# QuadroOLED.net
KiCad netlist of a schematic drawn in EAGLE
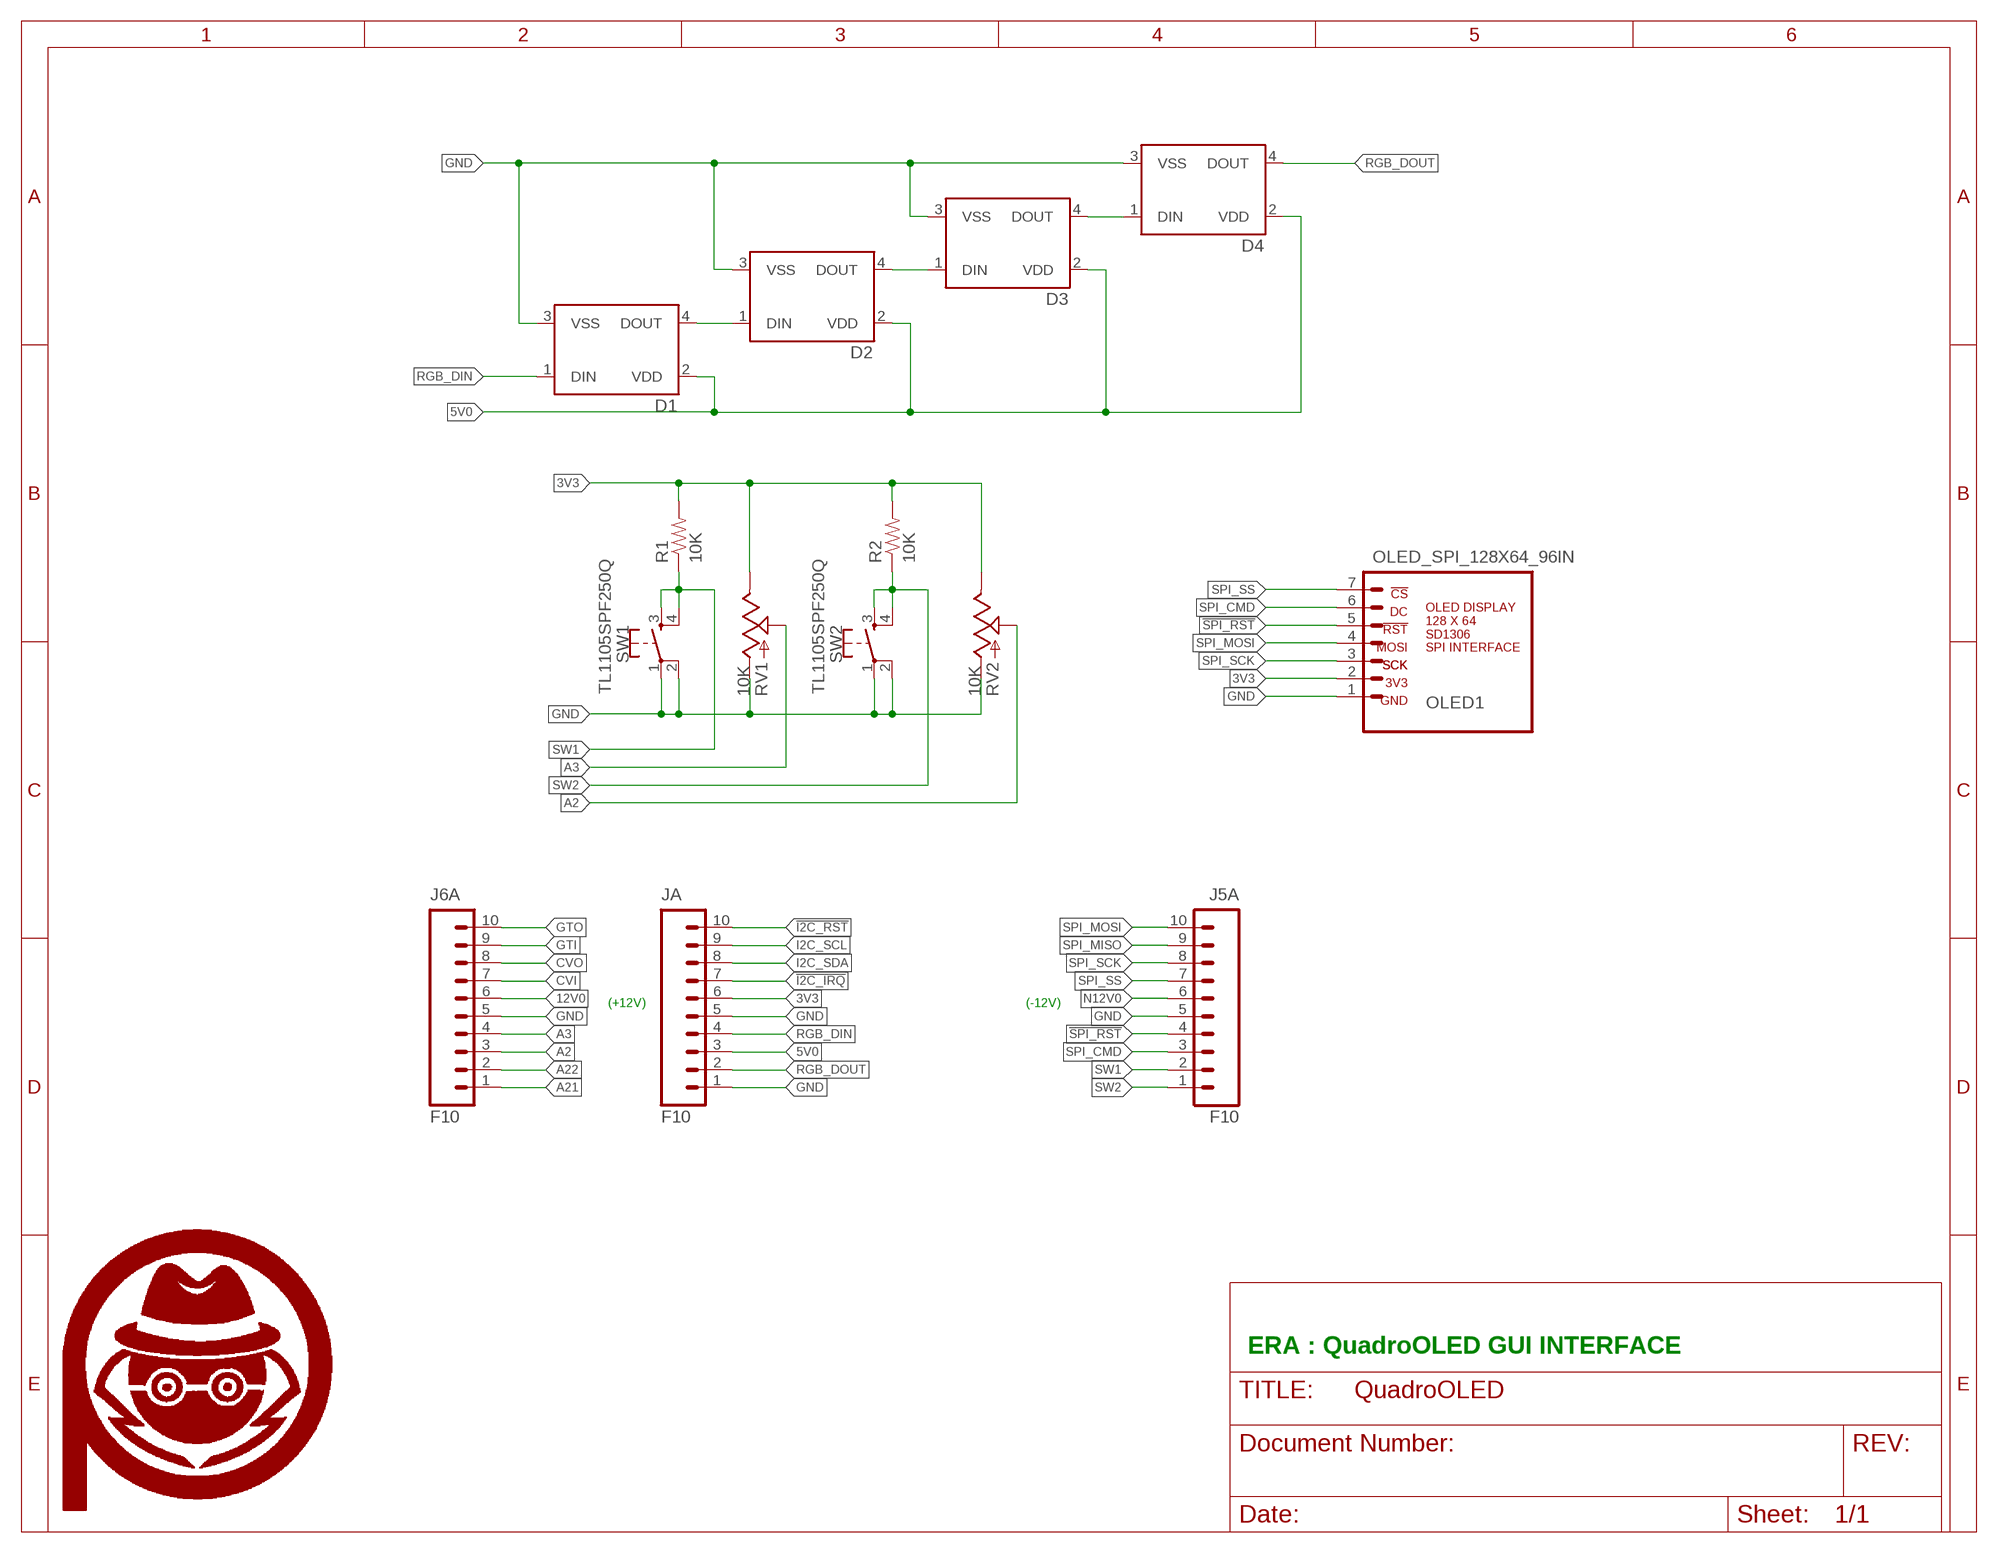
[diagram p0: schematic, sheet 1]

(export (version "E")
  (design (tool "Eeschema 10.0.6"))
  (components
    (comp (ref "D1")
      (value "WS2812B_PTH")
      (footprint "eagle-import:LED-RGB-THRU")
      (libsource (lib "eagle-import") (part "WS2812B_PTH"))
    )
    (comp (ref "D2")
      (value "WS2812B_PTH")
      (footprint "eagle-import:LED-RGB-THRU")
      (libsource (lib "eagle-import") (part "WS2812B_PTH"))
    )
    (comp (ref "D3")
      (value "WS2812B_PTH")
      (footprint "eagle-import:LED-RGB-THRU")
      (libsource (lib "eagle-import") (part "WS2812B_PTH"))
    )
    (comp (ref "D4")
      (value "WS2812B_PTH")
      (footprint "eagle-import:LED-RGB-THRU")
      (libsource (lib "eagle-import") (part "WS2812B_PTH"))
    )
    (comp (ref "J5A")
      (value "F10")
      (footprint "eagle-import:1X10_OCTO")
      (libsource (lib "eagle-import") (part "M10SILK_FEMALE_PTH"))
    )
    (comp (ref "J6A")
      (value "F10")
      (footprint "eagle-import:1X10_OCTO")
      (libsource (lib "eagle-import") (part "M10SILK_FEMALE_PTH"))
    )
    (comp (ref "JA")
      (value "F10")
      (footprint "eagle-import:1X10_OCTO")
      (libsource (lib "eagle-import") (part "M10SILK_FEMALE_PTH"))
    )
    (comp (ref "OLED1")
      (value "OLED_SPI_128X64_96IN")
      (footprint "eagle-import:OLED_128X64_96")
      (libsource (lib "eagle-import") (part "OLED_SPI_128X64_96IN"))
    )
    (comp (ref "R1")
      (value "10K")
      (footprint "eagle-import:0603-RES")
      (libsource (lib "eagle-import") (part "RESISTOR0603"))
    )
    (comp (ref "R2")
      (value "10K")
      (footprint "eagle-import:0603-RES")
      (libsource (lib "eagle-import") (part "RESISTOR0603"))
    )
    (comp (ref "RV1")
      (value "10K")
      (footprint "eagle-import:ALPS_POT")
      (libsource (lib "eagle-import") (part "POT"))
    )
    (comp (ref "RV2")
      (value "10K")
      (footprint "eagle-import:ALPS_POT")
      (libsource (lib "eagle-import") (part "POT"))
    )
    (comp (ref "SW1")
      (value "TL1105SPF250Q")
      (footprint "eagle-import:TL1105SPF250Q")
      (libsource (lib "eagle-import") (part "TL1105SPF250Q"))
    )
    (comp (ref "SW2")
      (value "TL1105SPF250Q")
      (footprint "eagle-import:TL1105SPF250Q")
      (libsource (lib "eagle-import") (part "TL1105SPF250Q"))
    )
    (comp (ref "U$1")
      (value "PA_LOGO_SYMLARGE")
      (footprint "eagle-import:PA_LOGO_AGENT_LRG_SYM")
      (libsource (lib "eagle-import") (part "PA_LOGO_SYMLARGE"))
    )
    (comp (ref "U$2")
      (value "PA_LOGO_SYMLARGE")
      (footprint "eagle-import:PA_LOGO_AGENT_LRG_SYM")
      (libsource (lib "eagle-import") (part "PA_LOGO_SYMLARGE"))
    )
  )
  (nets
    (net (code "1") (name "/~{I2C_IRQ}") (class "Default")
      (node (ref "JA") (pin "7") (pinfunction "7_7") (pintype "passive"))
    )
    (net (code "2") (name "/~{I2C_RST}") (class "Default")
      (node (ref "JA") (pin "10") (pinfunction "10_10") (pintype "passive"))
    )
    (net (code "3") (name "/~{SPI_RST}") (class "Default")
      (node (ref "J5A") (pin "4") (pinfunction "4_4") (pintype "passive"))
      (node (ref "OLED1") (pin "5") (pinfunction "5_5") (pintype "passive"))
    )
    (net (code "4") (name "3V3") (class "Default")
      (node (ref "JA") (pin "6") (pinfunction "6_6") (pintype "passive"))
      (node (ref "OLED1") (pin "2") (pinfunction "2_2") (pintype "passive"))
      (node (ref "R1") (pin "2") (pinfunction "2_2") (pintype "passive"))
      (node (ref "R2") (pin "2") (pinfunction "2_2") (pintype "passive"))
      (node (ref "RV1") (pin "P$1") (pinfunction "3_P$1") (pintype "passive"))
      (node (ref "RV2") (pin "P$1") (pinfunction "3_P$1") (pintype "passive"))
    )
    (net (code "5") (name "5V0") (class "Default")
      (node (ref "D1") (pin "2") (pinfunction "VDD_2") (pintype "power_in"))
      (node (ref "D2") (pin "2") (pinfunction "VDD_2") (pintype "power_in"))
      (node (ref "D3") (pin "2") (pinfunction "VDD_2") (pintype "power_in"))
      (node (ref "D4") (pin "2") (pinfunction "VDD_2") (pintype "power_in"))
      (node (ref "JA") (pin "3") (pinfunction "3_3") (pintype "passive"))
    )
    (net (code "6") (name "12V0") (class "Default")
      (node (ref "J6A") (pin "6") (pinfunction "6_6") (pintype "passive"))
    )
    (net (code "7") (name "A2") (class "Default")
      (node (ref "J6A") (pin "3") (pinfunction "3_3") (pintype "passive"))
      (node (ref "RV2") (pin "P$2") (pinfunction "2_P$2") (pintype "passive"))
    )
    (net (code "8") (name "A3") (class "Default")
      (node (ref "J6A") (pin "4") (pinfunction "4_4") (pintype "passive"))
      (node (ref "RV1") (pin "P$2") (pinfunction "2_P$2") (pintype "passive"))
    )
    (net (code "9") (name "A21") (class "Default")
      (node (ref "J6A") (pin "1") (pinfunction "1_1") (pintype "passive"))
    )
    (net (code "10") (name "A22") (class "Default")
      (node (ref "J6A") (pin "2") (pinfunction "2_2") (pintype "passive"))
    )
    (net (code "11") (name "CVI") (class "Default")
      (node (ref "J6A") (pin "7") (pinfunction "7_7") (pintype "passive"))
    )
    (net (code "12") (name "CVO") (class "Default")
      (node (ref "J6A") (pin "8") (pinfunction "8_8") (pintype "passive"))
    )
    (net (code "13") (name "GND") (class "Default")
      (node (ref "D1") (pin "3") (pinfunction "VSS_3") (pintype "power_in"))
      (node (ref "D2") (pin "3") (pinfunction "VSS_3") (pintype "power_in"))
      (node (ref "D3") (pin "3") (pinfunction "VSS_3") (pintype "power_in"))
      (node (ref "D4") (pin "3") (pinfunction "VSS_3") (pintype "power_in"))
      (node (ref "J5A") (pin "5") (pinfunction "5_5") (pintype "passive"))
      (node (ref "J6A") (pin "5") (pinfunction "5_5") (pintype "passive"))
      (node (ref "JA") (pin "1") (pinfunction "1_1") (pintype "passive"))
      (node (ref "JA") (pin "5") (pinfunction "5_5") (pintype "passive"))
      (node (ref "OLED1") (pin "1") (pinfunction "1_1") (pintype "passive"))
      (node (ref "RV1") (pin "P$3") (pinfunction "1_P$3") (pintype "passive"))
      (node (ref "RV2") (pin "P$3") (pinfunction "1_P$3") (pintype "passive"))
      (node (ref "SW1") (pin "1") (pinfunction "1_1") (pintype "passive"))
      (node (ref "SW1") (pin "2") (pinfunction "2_2") (pintype "passive"))
      (node (ref "SW2") (pin "1") (pinfunction "1_1") (pintype "passive"))
      (node (ref "SW2") (pin "2") (pinfunction "2_2") (pintype "passive"))
    )
    (net (code "14") (name "GTI") (class "Default")
      (node (ref "J6A") (pin "9") (pinfunction "9_9") (pintype "passive"))
    )
    (net (code "15") (name "GTO") (class "Default")
      (node (ref "J6A") (pin "10") (pinfunction "10_10") (pintype "passive"))
    )
    (net (code "16") (name "I2C_SCL") (class "Default")
      (node (ref "JA") (pin "9") (pinfunction "9_9") (pintype "passive"))
    )
    (net (code "17") (name "I2C_SDA") (class "Default")
      (node (ref "JA") (pin "8") (pinfunction "8_8") (pintype "passive"))
    )
    (net (code "18") (name "N12V0") (class "Default")
      (node (ref "J5A") (pin "6") (pinfunction "6_6") (pintype "passive"))
    )
    (net (code "19") (name "Net-(D1-DOUT)") (class "Default")
      (node (ref "D1") (pin "4") (pinfunction "DOUT_4") (pintype "output"))
      (node (ref "D2") (pin "1") (pinfunction "DIN_1") (pintype "input"))
    )
    (net (code "20") (name "Net-(D2-DOUT)") (class "Default")
      (node (ref "D2") (pin "4") (pinfunction "DOUT_4") (pintype "output"))
      (node (ref "D3") (pin "1") (pinfunction "DIN_1") (pintype "input"))
    )
    (net (code "21") (name "Net-(D3-DOUT)") (class "Default")
      (node (ref "D3") (pin "4") (pinfunction "DOUT_4") (pintype "output"))
      (node (ref "D4") (pin "1") (pinfunction "DIN_1") (pintype "input"))
    )
    (net (code "22") (name "RGB_DIN") (class "Default")
      (node (ref "D1") (pin "1") (pinfunction "DIN_1") (pintype "input"))
      (node (ref "JA") (pin "4") (pinfunction "4_4") (pintype "passive"))
    )
    (net (code "23") (name "RGB_DOUT") (class "Default")
      (node (ref "D4") (pin "4") (pinfunction "DOUT_4") (pintype "output"))
      (node (ref "JA") (pin "2") (pinfunction "2_2") (pintype "passive"))
    )
    (net (code "24") (name "SPI_CMD") (class "Default")
      (node (ref "J5A") (pin "3") (pinfunction "3_3") (pintype "passive"))
      (node (ref "OLED1") (pin "6") (pinfunction "6_6") (pintype "passive"))
    )
    (net (code "25") (name "SPI_MISO") (class "Default")
      (node (ref "J5A") (pin "9") (pinfunction "9_9") (pintype "passive"))
    )
    (net (code "26") (name "SPI_MOSI") (class "Default")
      (node (ref "J5A") (pin "10") (pinfunction "10_10") (pintype "passive"))
      (node (ref "OLED1") (pin "4") (pinfunction "4_4") (pintype "passive"))
    )
    (net (code "27") (name "SPI_SCK") (class "Default")
      (node (ref "J5A") (pin "8") (pinfunction "8_8") (pintype "passive"))
      (node (ref "OLED1") (pin "3") (pinfunction "3_3") (pintype "passive"))
    )
    (net (code "28") (name "SPI_SS") (class "Default")
      (node (ref "J5A") (pin "7") (pinfunction "7_7") (pintype "passive"))
      (node (ref "OLED1") (pin "7") (pinfunction "7_7") (pintype "passive"))
    )
    (net (code "29") (name "SW1") (class "Default")
      (node (ref "J5A") (pin "2") (pinfunction "2_2") (pintype "passive"))
      (node (ref "R1") (pin "1") (pinfunction "1_1") (pintype "passive"))
      (node (ref "SW1") (pin "3") (pinfunction "3_3") (pintype "passive"))
      (node (ref "SW1") (pin "4") (pinfunction "4_4") (pintype "passive"))
    )
    (net (code "30") (name "SW2") (class "Default")
      (node (ref "J5A") (pin "1") (pinfunction "1_1") (pintype "passive"))
      (node (ref "R2") (pin "1") (pinfunction "1_1") (pintype "passive"))
      (node (ref "SW2") (pin "3") (pinfunction "3_3") (pintype "passive"))
      (node (ref "SW2") (pin "4") (pinfunction "4_4") (pintype "passive"))
    )
  )
)
